# EtherCAT_Sheet.net
KiCad netlist of a schematic drawn in Altium Designer
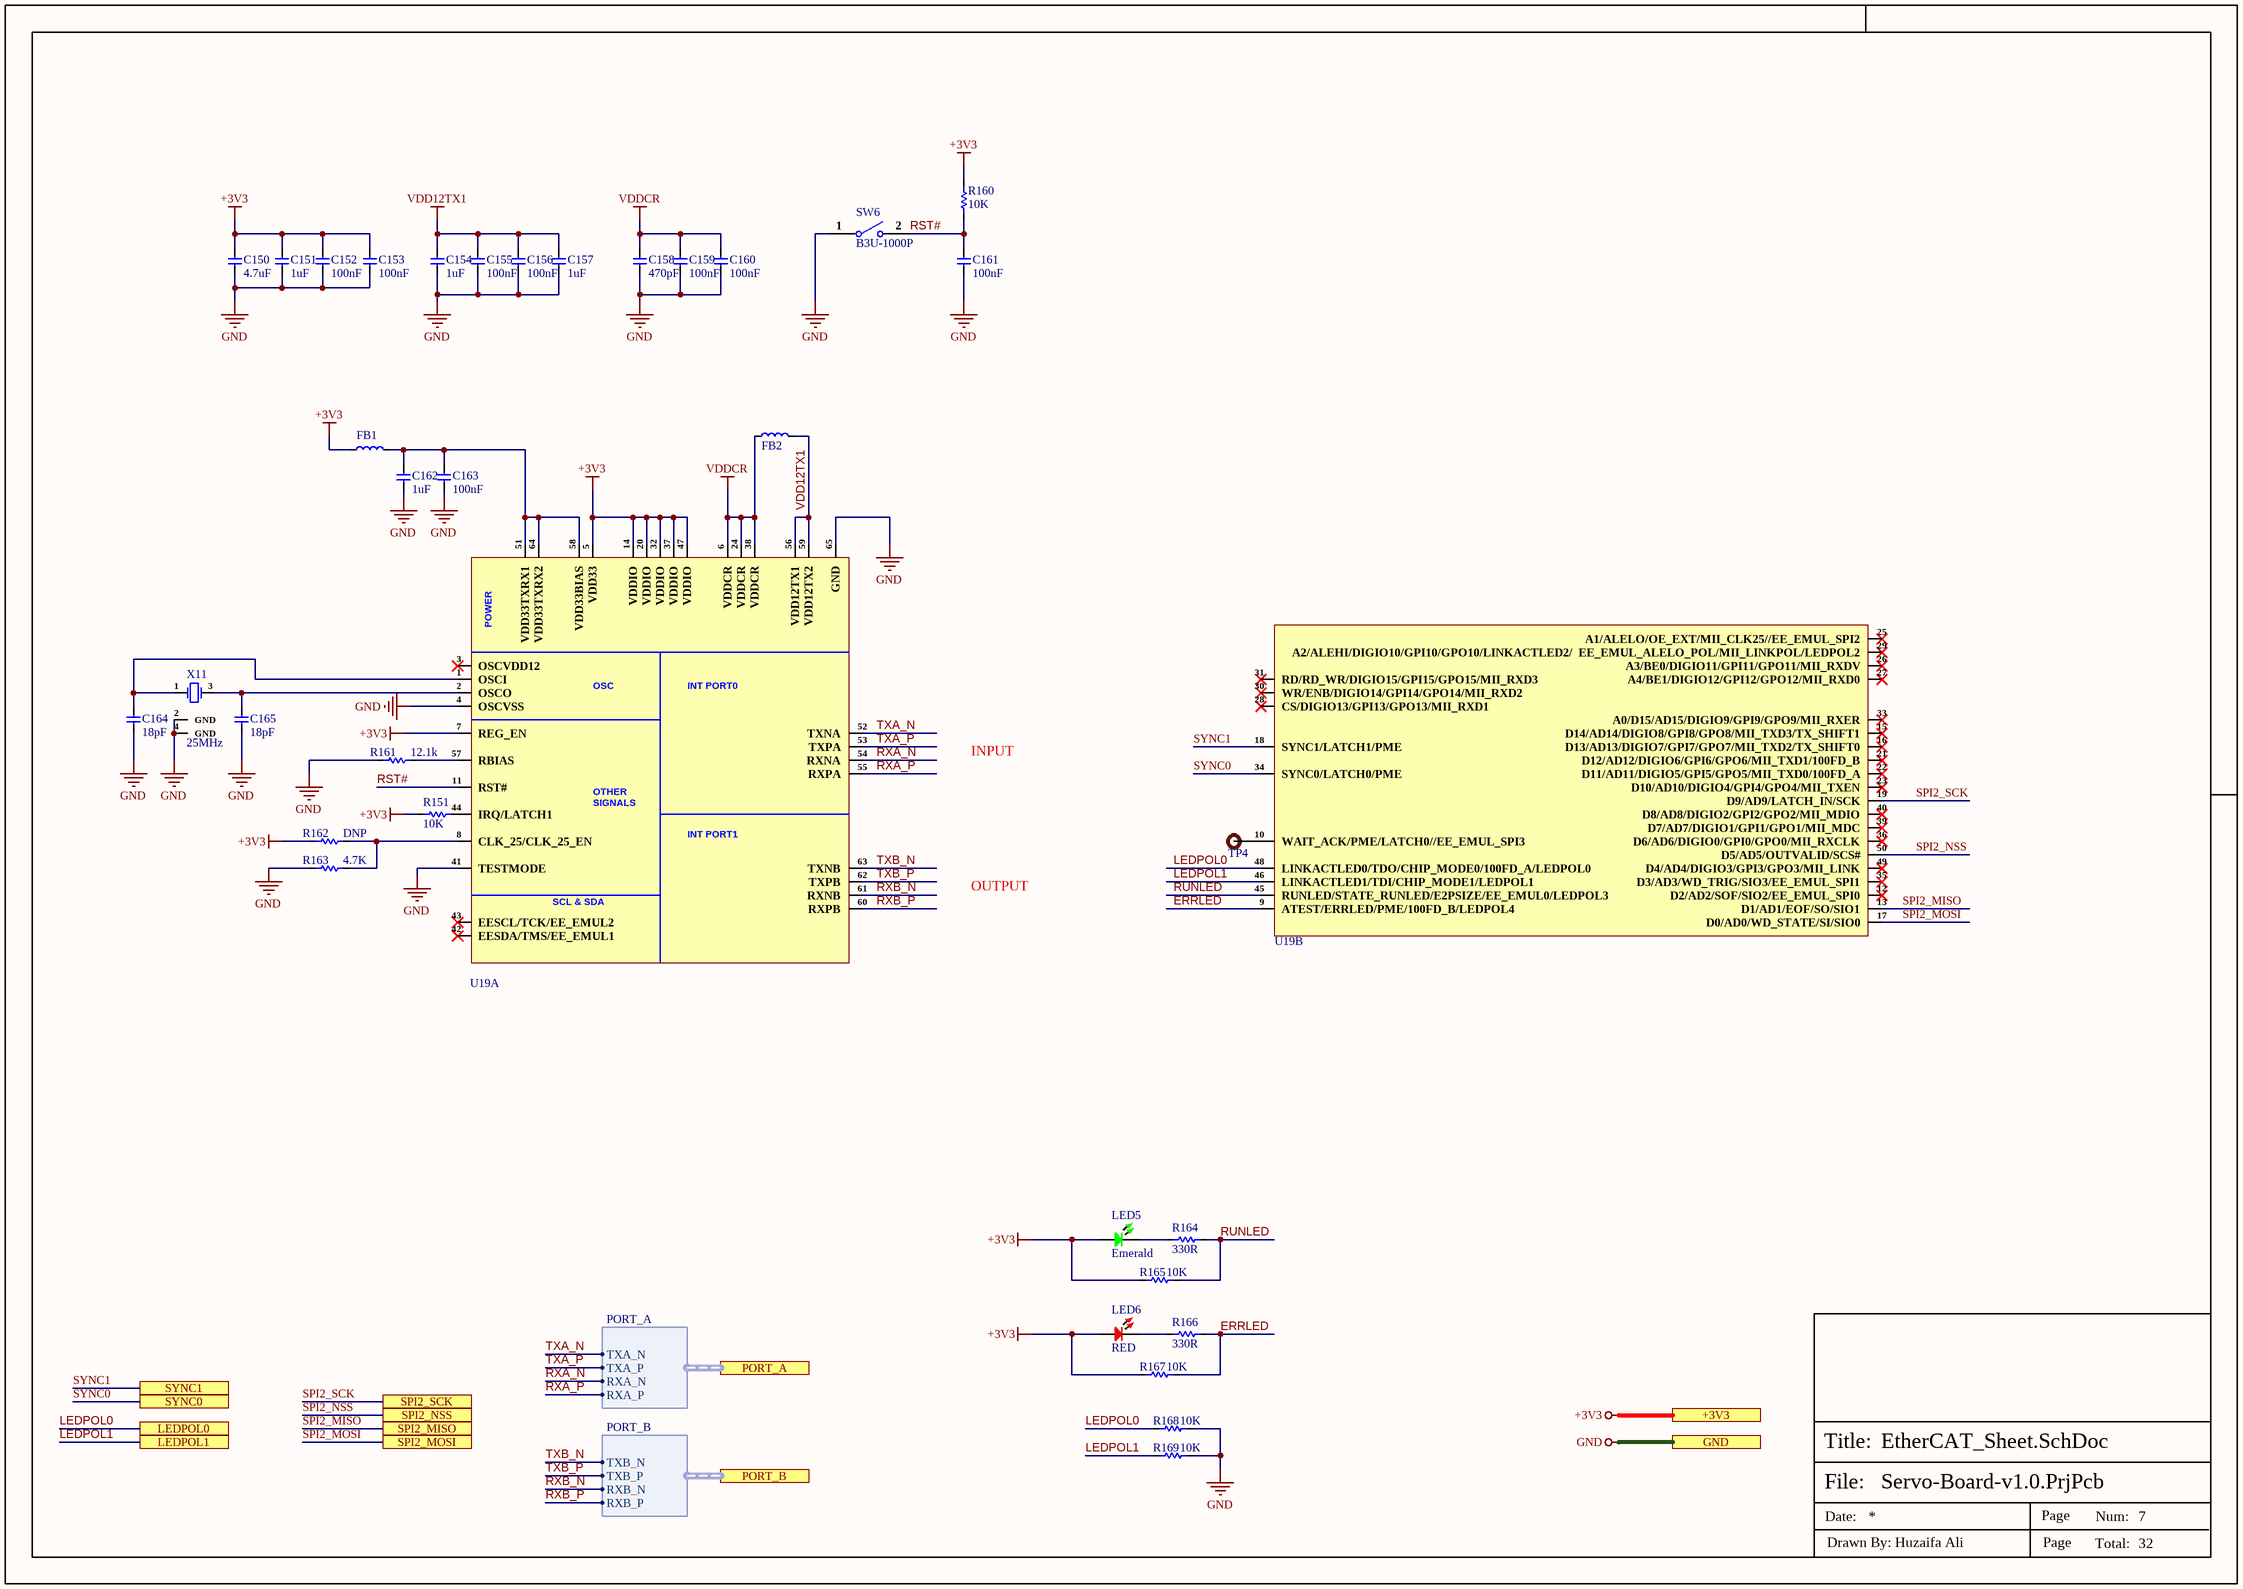
[diagram p0: EtherCAT_Sheet.SchDoc]

(export (version "E")
  (design (tool "Eeschema 10.0.6"))
  (components
    (comp (ref "C150")
      (value "4.7uF")
      (footprint "Cap-0402")
      (description "CAP CER 4.7UF 10V X5R 0402")
      (fields
        (field (name "MANUFACTURER") "Yageo")
        (field (name "MANUFACTURER PART NUMBER") "CC0402KRX5R6BB475")
      )
      (libsource (lib "eSpark Libraries") (part "CC0402KRX5R6BB475"))
    )
    (comp (ref "C151")
      (value "1uF")
      (footprint "Cap-0402")
      (description "CAP CER 1UF 10V X5R 0402")
      (fields
        (field (name "MANUFACTURER") "Yageo")
        (field (name "MANUFACTURER PART NUMBER") "CC0402KRX5R6BB105")
      )
      (libsource (lib "eSpark Libraries") (part "CC0402KRX5R6BB105"))
    )
    (comp (ref "C152")
      (value "100nF")
      (footprint "cap-0402")
      (description "CAP CER 0.1UF 50V X7R 0402")
      (fields
        (field (name "MANUFACTURER") "TDK")
        (field (name "MANUFACTURER PART NUMBER") "C1005X7R1H104KT000F")
      )
      (libsource (lib "eSpark Libraries") (part "C1005X7R1H104KT000F"))
    )
    (comp (ref "C153")
      (value "100nF")
      (footprint "cap-0402")
      (description "CAP CER 0.1UF 50V X7R 0402")
      (fields
        (field (name "MANUFACTURER") "TDK")
        (field (name "MANUFACTURER PART NUMBER") "C1005X7R1H104KT000F")
      )
      (libsource (lib "eSpark Libraries") (part "C1005X7R1H104KT000F"))
    )
    (comp (ref "C154")
      (value "1uF")
      (footprint "Cap-0402")
      (description "CAP CER 1UF 10V X5R 0402")
      (fields
        (field (name "MANUFACTURER") "Yageo")
        (field (name "MANUFACTURER PART NUMBER") "CC0402KRX5R6BB105")
      )
      (libsource (lib "eSpark Libraries") (part "CC0402KRX5R6BB105"))
    )
    (comp (ref "C155")
      (value "100nF")
      (footprint "cap-0402")
      (description "CAP CER 0.1UF 50V X7R 0402")
      (fields
        (field (name "MANUFACTURER") "TDK")
        (field (name "MANUFACTURER PART NUMBER") "C1005X7R1H104KT000F")
      )
      (libsource (lib "eSpark Libraries") (part "C1005X7R1H104KT000F"))
    )
    (comp (ref "C156")
      (value "100nF")
      (footprint "cap-0402")
      (description "CAP CER 0.1UF 50V X7R 0402")
      (fields
        (field (name "MANUFACTURER") "TDK")
        (field (name "MANUFACTURER PART NUMBER") "C1005X7R1H104KT000F")
      )
      (libsource (lib "eSpark Libraries") (part "C1005X7R1H104KT000F"))
    )
    (comp (ref "C157")
      (value "1uF")
      (footprint "Cap-0402")
      (description "CAP CER 1UF 10V X5R 0402")
      (fields
        (field (name "MANUFACTURER") "Yageo")
        (field (name "MANUFACTURER PART NUMBER") "CC0402KRX5R6BB105")
      )
      (libsource (lib "eSpark Libraries") (part "CC0402KRX5R6BB105"))
    )
    (comp (ref "C158")
      (value "470pF")
      (footprint "Cap-0603")
      (description "CAP CER 470PF 50V X7R 0603")
      (fields
        (field (name "MANUFACTURER") "Walsin Technologies")
        (field (name "MANUFACTURER PART NUMBER") "0603B471K500CT")
      )
      (libsource (lib "eSpark Libraries") (part "0603B471K500CT"))
    )
    (comp (ref "C159")
      (value "100nF")
      (footprint "cap-0402")
      (description "CAP CER 0.1UF 50V X7R 0402")
      (fields
        (field (name "MANUFACTURER") "TDK")
        (field (name "MANUFACTURER PART NUMBER") "C1005X7R1H104KT000F")
      )
      (libsource (lib "eSpark Libraries") (part "C1005X7R1H104KT000F"))
    )
    (comp (ref "C160")
      (value "100nF")
      (footprint "cap-0402")
      (description "CAP CER 0.1UF 50V X7R 0402")
      (fields
        (field (name "MANUFACTURER") "TDK")
        (field (name "MANUFACTURER PART NUMBER") "C1005X7R1H104KT000F")
      )
      (libsource (lib "eSpark Libraries") (part "C1005X7R1H104KT000F"))
    )
    (comp (ref "C161")
      (value "100nF")
      (footprint "cap-0402")
      (description "CAP CER 0.1UF 50V X7R 0402")
      (fields
        (field (name "MANUFACTURER") "TDK")
        (field (name "MANUFACTURER PART NUMBER") "C1005X7R1H104KT000F")
      )
      (libsource (lib "eSpark Libraries") (part "C1005X7R1H104KT000F"))
    )
    (comp (ref "C162")
      (value "1uF")
      (footprint "Cap-0402")
      (description "CAP CER 1UF 10V X5R 0402")
      (fields
        (field (name "MANUFACTURER") "Yageo")
        (field (name "MANUFACTURER PART NUMBER") "CC0402KRX5R6BB105")
      )
      (libsource (lib "eSpark Libraries") (part "CC0402KRX5R6BB105"))
    )
    (comp (ref "C163")
      (value "100nF")
      (footprint "cap-0402")
      (description "CAP CER 0.1UF 50V X7R 0402")
      (fields
        (field (name "MANUFACTURER") "TDK")
        (field (name "MANUFACTURER PART NUMBER") "C1005X7R1H104KT000F")
      )
      (libsource (lib "eSpark Libraries") (part "C1005X7R1H104KT000F"))
    )
    (comp (ref "C164")
      (value "18pF")
      (footprint "Cap-0402")
      (description "CAP CER 18PF 50V C0G/NP0 0402")
      (fields
        (field (name "MANUFACTURER") "Murata")
        (field (name "MANUFACTURER PART NUMBER") "GCM1555C1H180GA16D")
      )
      (libsource (lib "eSpark Libraries") (part "GCM1555C1H180GA16D"))
    )
    (comp (ref "C165")
      (value "18pF")
      (footprint "Cap-0402")
      (description "CAP CER 18PF 50V C0G/NP0 0402")
      (fields
        (field (name "MANUFACTURER") "Murata")
        (field (name "MANUFACTURER PART NUMBER") "GCM1555C1H180GA16D")
      )
      (libsource (lib "eSpark Libraries") (part "GCM1555C1H180GA16D"))
    )
    (comp (ref "FB1")
      (value "BLM15PG100SN1D")
      (footprint "IND-0402")
      (description "FERRITE BEAD 10 OHM 0402 1LN")
      (fields (field (name "MANUFACTURER") "Murata") (field (name "TOLERANCE") "25%"))
      (libsource (lib "eSpark Libraries") (part "BLM15PG100SN1D"))
    )
    (comp (ref "FB2")
      (value "BLM15PG100SN1D")
      (footprint "IND-0402")
      (description "FERRITE BEAD 10 OHM 0402 1LN")
      (fields (field (name "MANUFACTURER") "Murata") (field (name "TOLERANCE") "25%"))
      (libsource (lib "eSpark Libraries") (part "BLM15PG100SN1D"))
    )
    (comp (ref "LED5")
      (value "Emerald")
      (footprint "LED-0603")
      (description "Emerald 0603 Light Emitting Diodes (LED) ROHS")
      (fields
        (field (name "MANUFACTURER") "Foshan NationStar Optoelectronics")
        (field (name "MANUFACTURER PART NUMBER") "NCD0603G2")
      )
      (libsource (lib "eSpark Libraries") (part "NCD0603G2"))
    )
    (comp (ref "LED6")
      (value "RED")
      (footprint "LED-0603")
      (description "RED LED 0603 Light Emitting Diodes")
      (fields
        (field (name "MANUFACTURER") "Foshan NationStar Optoelectronics")
        (field (name "MANUFACTURER PART NUMBER") "NCD0603R3")
      )
      (libsource (lib "eSpark Libraries") (part "NCD0603R3"))
    )
    (comp (ref "R151")
      (value "10K")
      (footprint "Res-0402")
      (description "RES 10K OHM 1% 1/16W 0402")
      (fields
        (field (name "MANUFACTURER") "Yageo")
        (field (name "MANUFACTURER PART NUMBER") "RC0402FR-0710KL")
      )
      (libsource (lib "eSpark Libraries") (part "RC0402FR-0710KL"))
    )
    (comp (ref "R160")
      (value "10K")
      (footprint "Res-0402")
      (description "RES 10K OHM 1% 1/16W 0402")
      (fields
        (field (name "MANUFACTURER") "Yageo")
        (field (name "MANUFACTURER PART NUMBER") "RC0402FR-0710KL")
      )
      (libsource (lib "eSpark Libraries") (part "RC0402FR-0710KL"))
    )
    (comp (ref "R161")
      (value "12.1k")
      (footprint "Res-0402")
      (description "RES SMD 12.1KOHM 0.1% 1/16W 0402")
      (fields
        (field (name "MANUFACTURER") "Yageo")
        (field (name "MANUFACTURER PART NUMBER") "RT0402BRD0712K1L")
      )
      (libsource (lib "eSpark Libraries") (part "RT0402BRD0712K1L"))
    )
    (comp (ref "R162")
      (value "DNP")
      (footprint "Res-0402")
      (description "RES 4.7K OHM 1% 1/16W 0402")
      (fields
        (field (name "MANUFACTURER") "Yageo")
        (field (name "MANUFACTURER PART NUMBER") "RC0402FR-074K7L")
      )
      (libsource (lib "eSpark Libraries") (part "RC0402FR-074K7L"))
    )
    (comp (ref "R163")
      (value "4.7K")
      (footprint "Res-0402")
      (description "RES 4.7K OHM 1% 1/16W 0402")
      (fields
        (field (name "MANUFACTURER") "Yageo")
        (field (name "MANUFACTURER PART NUMBER") "RC0402FR-074K7L")
      )
      (libsource (lib "eSpark Libraries") (part "RC0402FR-074K7L"))
    )
    (comp (ref "R164")
      (value "330R")
      (footprint "Res-0603")
      (description "RES  SMD 330R 100 mW 0603")
      (fields
        (field (name "MANUFACTURER") "Yageo")
        (field (name "MANUFACTURER PART NUMBER") "RC0603JR-07330RL")
      )
      (libsource (lib "eSpark Libraries") (part "RC0603JR-07330RL"))
    )
    (comp (ref "R165")
      (value "10K")
      (footprint "Res-0402")
      (description "RES 10K OHM 1% 1/16W 0402")
      (fields
        (field (name "MANUFACTURER") "Yageo")
        (field (name "MANUFACTURER PART NUMBER") "RC0402FR-0710KL")
      )
      (libsource (lib "eSpark Libraries") (part "RC0402FR-0710KL"))
    )
    (comp (ref "R166")
      (value "330R")
      (footprint "Res-0603")
      (description "RES  SMD 330R 100 mW 0603")
      (fields
        (field (name "MANUFACTURER") "Yageo")
        (field (name "MANUFACTURER PART NUMBER") "RC0603JR-07330RL")
      )
      (libsource (lib "eSpark Libraries") (part "RC0603JR-07330RL"))
    )
    (comp (ref "R167")
      (value "10K")
      (footprint "Res-0402")
      (description "RES 10K OHM 1% 1/16W 0402")
      (fields
        (field (name "MANUFACTURER") "Yageo")
        (field (name "MANUFACTURER PART NUMBER") "RC0402FR-0710KL")
      )
      (libsource (lib "eSpark Libraries") (part "RC0402FR-0710KL"))
    )
    (comp (ref "R168")
      (value "10K")
      (footprint "Res-0402")
      (description "RES 10K OHM 1% 1/16W 0402")
      (fields
        (field (name "MANUFACTURER") "Yageo")
        (field (name "MANUFACTURER PART NUMBER") "RC0402FR-0710KL")
      )
      (libsource (lib "eSpark Libraries") (part "RC0402FR-0710KL"))
    )
    (comp (ref "R169")
      (value "10K")
      (footprint "Res-0402")
      (description "RES 10K OHM 1% 1/16W 0402")
      (fields
        (field (name "MANUFACTURER") "Yageo")
        (field (name "MANUFACTURER PART NUMBER") "RC0402FR-0710KL")
      )
      (libsource (lib "eSpark Libraries") (part "RC0402FR-0710KL"))
    )
    (comp (ref "SW6")
      (value "B3U-1000P")
      (footprint "B3U-1000P")
      (description "SWITCH TACTILE SPST-NO 0.05A 12V")
      (fields (field (name "MANUFACTURER") "Omron") (field (name "LCSC PART NUMBER") "C231329"))
      (libsource (lib "eSpark Libraries") (part "B3U-1000P"))
    )
    (comp (ref "TP4")
      (value "TEST POINT")
      (footprint "Test-point")
      (description "Test Point ON")
      (libsource (lib "eSpark Libraries") (part "TEST POINT"))
    )
    (comp (ref "U19")
      (value "LAN9253-SVB QFN64")
      (footprint "QFN-64-EP(9x9)")
      (description "2/3-PORT ETHERCAT SLAVE CTLR")
      (fields
        (field (name "MANUFACTURER") "Microchip")
        (field (name "MANUFACTURER PART NUMBER") "LAN9253-I/R4X")
      )
      (libsource (lib "eSpark Libraries") (part "LAN9253-SVB QFN64"))
    )
    (comp (ref "X11")
      (value "25MHz")
      (footprint "SMD3225-4P")
      (description "25MHz 贴片晶振 18pF ±10ppm ±20ppm SMD3225-4P Crystals ROHS")
      (fields (field (name "LCSC PART NUMBER") "C70593") (field (name "MANUFACTURER") "YXC"))
      (libsource (lib "eSpark Libraries") (part "X322525MRB4SI"))
    )
  )
  (nets
    (net (code "3") (name "+3V3") (class "Default")
      (node (ref "C150") (pin "2") (pinfunction "2_2") (pintype "passive"))
      (node (ref "C151") (pin "2") (pinfunction "2_2") (pintype "passive"))
      (node (ref "C152") (pin "2") (pinfunction "2_2") (pintype "passive"))
      (node (ref "C153") (pin "2") (pinfunction "2_2") (pintype "passive"))
      (node (ref "FB1") (pin "1") (pinfunction "1_1") (pintype "passive"))
      (node (ref "LED5") (pin "1") (pinfunction "1_1") (pintype "passive"))
      (node (ref "LED6") (pin "1") (pinfunction "1_1") (pintype "passive"))
      (node (ref "R151") (pin "1") (pinfunction "1_1") (pintype "passive"))
      (node (ref "R160") (pin "1") (pinfunction "1_1") (pintype "passive"))
      (node (ref "R162") (pin "1") (pinfunction "1_1") (pintype "passive"))
      (node (ref "R165") (pin "2") (pinfunction "2_2") (pintype "passive"))
      (node (ref "R167") (pin "2") (pinfunction "2_2") (pintype "passive"))
      (node (ref "U19") (pin "14") (pinfunction "VDDIO_14") (pintype "passive"))
      (node (ref "U19") (pin "20") (pinfunction "VDDIO_20") (pintype "passive"))
      (node (ref "U19") (pin "32") (pinfunction "VDDIO_32") (pintype "passive"))
      (node (ref "U19") (pin "37") (pinfunction "VDDIO_37") (pintype "passive"))
      (node (ref "U19") (pin "47") (pinfunction "VDDIO_47") (pintype "passive"))
      (node (ref "U19") (pin "5") (pinfunction "VDD33_5") (pintype "passive"))
      (node (ref "U19") (pin "7") (pinfunction "REG_EN_7") (pintype "passive"))
    )
    (net (code "4") (name "/ERRLED") (class "Default")
      (node (ref "R166") (pin "2") (pinfunction "2_2") (pintype "passive"))
      (node (ref "R167") (pin "1") (pinfunction "1_1") (pintype "passive"))
      (node (ref "U19") (pin "9") (pinfunction "ATEST/ERRLED/PME/100FD_B/LEDPOL4_9") (pintype "passive"))
    )
    (net (code "5") (name "/LEDPOL0") (class "Default")
      (node (ref "R168") (pin "2") (pinfunction "2_2") (pintype "passive"))
      (node (ref "U19") (pin "48") (pinfunction "LINKACTLED0/TDO/CHIP_MODE0/100FD_A/LEDPOL0_48") (pintype "passive"))
    )
    (net (code "6") (name "/LEDPOL1") (class "Default")
      (node (ref "R169") (pin "2") (pinfunction "2_2") (pintype "passive"))
      (node (ref "U19") (pin "46") (pinfunction "LINKACTLED1/TDI/CHIP_MODE1/LEDPOL1_46") (pintype "passive"))
    )
    (net (code "7") (name "/RST#") (class "Default")
      (node (ref "C161") (pin "2") (pinfunction "2_2") (pintype "passive"))
      (node (ref "R160") (pin "2") (pinfunction "2_2") (pintype "passive"))
      (node (ref "SW6") (pin "2") (pinfunction "2_2") (pintype "passive"))
      (node (ref "U19") (pin "11") (pinfunction "RST#_11") (pintype "passive"))
    )
    (net (code "8") (name "/RUNLED") (class "Default")
      (node (ref "R164") (pin "2") (pinfunction "2_2") (pintype "passive"))
      (node (ref "R165") (pin "1") (pinfunction "1_1") (pintype "passive"))
      (node (ref "U19") (pin "45") (pinfunction "RUNLED/STATE_RUNLED/E2PSIZE/EE_EMUL0/LEDPOL3_45") (pintype "passive"))
    )
    (net (code "9") (name "/RXA_N") (class "Default")
      (node (ref "U19") (pin "54") (pinfunction "RXNA_54") (pintype "passive"))
    )
    (net (code "10") (name "/RXA_P") (class "Default")
      (node (ref "U19") (pin "55") (pinfunction "RXPA_55") (pintype "passive"))
    )
    (net (code "11") (name "/RXB_N") (class "Default")
      (node (ref "U19") (pin "61") (pinfunction "RXNB_61") (pintype "passive"))
    )
    (net (code "12") (name "/RXB_P") (class "Default")
      (node (ref "U19") (pin "60") (pinfunction "RXPB_60") (pintype "passive"))
    )
    (net (code "13") (name "/SPI2_MISO") (class "Default")
      (node (ref "U19") (pin "13") (pinfunction "D1/AD1/EOF/SO/SIO1_13") (pintype "passive"))
    )
    (net (code "14") (name "/SPI2_MOSI") (class "Default")
      (node (ref "U19") (pin "17") (pinfunction "D0/AD0/WD_STATE/SI/SIO0_17") (pintype "passive"))
    )
    (net (code "15") (name "/SPI2_NSS") (class "Default")
      (node (ref "U19") (pin "50") (pinfunction "D5/AD5/OUTVALID/SCS#_50") (pintype "passive"))
    )
    (net (code "16") (name "/SPI2_SCK") (class "Default")
      (node (ref "U19") (pin "19") (pinfunction "D9/AD9/LATCH_IN/SCK_19") (pintype "passive"))
    )
    (net (code "17") (name "/SYNC0") (class "Default")
      (node (ref "U19") (pin "34") (pinfunction "SYNC0/LATCH0/PME_34") (pintype "passive"))
    )
    (net (code "18") (name "/SYNC1") (class "Default")
      (node (ref "U19") (pin "18") (pinfunction "SYNC1/LATCH1/PME_18") (pintype "passive"))
    )
    (net (code "19") (name "/TXA_N") (class "Default")
      (node (ref "U19") (pin "52") (pinfunction "TXNA_52") (pintype "passive"))
    )
    (net (code "20") (name "/TXA_P") (class "Default")
      (node (ref "U19") (pin "53") (pinfunction "TXPA_53") (pintype "passive"))
    )
    (net (code "21") (name "/TXB_N") (class "Default")
      (node (ref "U19") (pin "63") (pinfunction "TXNB_63") (pintype "passive"))
    )
    (net (code "22") (name "/TXB_P") (class "Default")
      (node (ref "U19") (pin "62") (pinfunction "TXPB_62") (pintype "passive"))
    )
    (net (code "25") (name "GND") (class "Default")
      (node (ref "C150") (pin "1") (pinfunction "1_1") (pintype "passive"))
      (node (ref "C151") (pin "1") (pinfunction "1_1") (pintype "passive"))
      (node (ref "C152") (pin "1") (pinfunction "1_1") (pintype "passive"))
      (node (ref "C153") (pin "1") (pinfunction "1_1") (pintype "passive"))
      (node (ref "C154") (pin "1") (pinfunction "1_1") (pintype "passive"))
      (node (ref "C155") (pin "1") (pinfunction "1_1") (pintype "passive"))
      (node (ref "C156") (pin "1") (pinfunction "1_1") (pintype "passive"))
      (node (ref "C157") (pin "1") (pinfunction "1_1") (pintype "passive"))
      (node (ref "C158") (pin "1") (pinfunction "1_1") (pintype "passive"))
      (node (ref "C159") (pin "1") (pinfunction "1_1") (pintype "passive"))
      (node (ref "C160") (pin "1") (pinfunction "1_1") (pintype "passive"))
      (node (ref "C161") (pin "1") (pinfunction "1_1") (pintype "passive"))
      (node (ref "C162") (pin "1") (pinfunction "1_1") (pintype "passive"))
      (node (ref "C163") (pin "1") (pinfunction "1_1") (pintype "passive"))
      (node (ref "C164") (pin "2") (pinfunction "2_2") (pintype "passive"))
      (node (ref "C165") (pin "2") (pinfunction "2_2") (pintype "passive"))
      (node (ref "R161") (pin "1") (pinfunction "1_1") (pintype "passive"))
      (node (ref "R163") (pin "1") (pinfunction "1_1") (pintype "passive"))
      (node (ref "R168") (pin "1") (pinfunction "1_1") (pintype "passive"))
      (node (ref "R169") (pin "1") (pinfunction "1_1") (pintype "passive"))
      (node (ref "SW6") (pin "1") (pinfunction "1_1") (pintype "passive"))
      (node (ref "U19") (pin "4") (pinfunction "OSCVSS_4") (pintype "passive"))
      (node (ref "U19") (pin "41") (pinfunction "TESTMODE_41") (pintype "passive"))
      (node (ref "U19") (pin "65") (pinfunction "GND_65") (pintype "passive"))
      (node (ref "X11") (pin "2") (pinfunction "GND_2") (pintype "passive"))
      (node (ref "X11") (pin "4") (pinfunction "GND_4") (pintype "passive"))
    )
    (net (code "26") (name "Net-(LED5-Pad2)") (class "Default")
      (node (ref "LED5") (pin "2") (pinfunction "2_2") (pintype "passive"))
      (node (ref "R164") (pin "1") (pinfunction "1_1") (pintype "passive"))
    )
    (net (code "27") (name "Net-(LED6-Pad2)") (class "Default")
      (node (ref "LED6") (pin "2") (pinfunction "2_2") (pintype "passive"))
      (node (ref "R166") (pin "1") (pinfunction "1_1") (pintype "passive"))
    )
    (net (code "28") (name "Net-(U19A-CLK_25{slash}CLK_25_EN)") (class "Default")
      (node (ref "R162") (pin "2") (pinfunction "2_2") (pintype "passive"))
      (node (ref "R163") (pin "2") (pinfunction "2_2") (pintype "passive"))
      (node (ref "U19") (pin "8") (pinfunction "CLK_25/CLK_25_EN_8") (pintype "passive"))
    )
    (net (code "29") (name "Net-(U19A-IRQ{slash}LATCH1)") (class "Default")
      (node (ref "R151") (pin "2") (pinfunction "2_2") (pintype "passive"))
      (node (ref "U19") (pin "44") (pinfunction "IRQ/LATCH1_44") (pintype "passive"))
    )
    (net (code "30") (name "Net-(U19A-OSCI)") (class "Default")
      (node (ref "C164") (pin "1") (pinfunction "1_1") (pintype "passive"))
      (node (ref "U19") (pin "1") (pinfunction "OSCI_1") (pintype "passive"))
      (node (ref "X11") (pin "1") (pinfunction "CRYSTAL_1") (pintype "passive"))
    )
    (net (code "31") (name "Net-(U19A-OSCO)") (class "Default")
      (node (ref "C165") (pin "1") (pinfunction "1_1") (pintype "passive"))
      (node (ref "U19") (pin "2") (pinfunction "OSCO_2") (pintype "passive"))
      (node (ref "X11") (pin "3") (pinfunction "CRYSTAL_3") (pintype "passive"))
    )
    (net (code "32") (name "Net-(U19A-RBIAS)") (class "Default")
      (node (ref "R161") (pin "2") (pinfunction "2_2") (pintype "passive"))
      (node (ref "U19") (pin "57") (pinfunction "RBIAS_57") (pintype "passive"))
    )
    (net (code "33") (name "Net-(U19A-VDD33BIAS)") (class "Default")
      (node (ref "C162") (pin "2") (pinfunction "2_2") (pintype "passive"))
      (node (ref "C163") (pin "2") (pinfunction "2_2") (pintype "passive"))
      (node (ref "FB1") (pin "2") (pinfunction "2_2") (pintype "passive"))
      (node (ref "U19") (pin "51") (pinfunction "VDD33TXRX1_51") (pintype "passive"))
      (node (ref "U19") (pin "58") (pinfunction "VDD33BIAS_58") (pintype "passive"))
      (node (ref "U19") (pin "64") (pinfunction "VDD33TXRX2_64") (pintype "passive"))
    )
    (net (code "34") (name "Net-(U19B-WAIT_ACK{slash}PME{slash}LATCH0{slash}{slash}EE_EMUL_SPI3)") (class "Default")
      (node (ref "TP4") (pin "1") (pinfunction "1_1") (pintype "passive"))
      (node (ref "U19") (pin "10") (pinfunction "WAIT_ACK/PME/LATCH0//EE_EMUL_SPI3_10") (pintype "passive"))
    )
    (net (code "35") (name "VDD12TX1") (class "Default")
      (node (ref "C154") (pin "2") (pinfunction "2_2") (pintype "passive"))
      (node (ref "C155") (pin "2") (pinfunction "2_2") (pintype "passive"))
      (node (ref "C156") (pin "2") (pinfunction "2_2") (pintype "passive"))
      (node (ref "C157") (pin "2") (pinfunction "2_2") (pintype "passive"))
      (node (ref "FB2") (pin "2") (pinfunction "2_2") (pintype "passive"))
      (node (ref "U19") (pin "56") (pinfunction "VDD12TX1_56") (pintype "passive"))
      (node (ref "U19") (pin "59") (pinfunction "VDD12TX2_59") (pintype "passive"))
    )
    (net (code "36") (name "VDDCR") (class "Default")
      (node (ref "C158") (pin "2") (pinfunction "2_2") (pintype "passive"))
      (node (ref "C159") (pin "2") (pinfunction "2_2") (pintype "passive"))
      (node (ref "C160") (pin "2") (pinfunction "2_2") (pintype "passive"))
      (node (ref "FB2") (pin "1") (pinfunction "1_1") (pintype "passive"))
      (node (ref "U19") (pin "24") (pinfunction "VDDCR_24") (pintype "passive"))
      (node (ref "U19") (pin "38") (pinfunction "VDDCR_38") (pintype "passive"))
      (node (ref "U19") (pin "6") (pinfunction "VDDCR_6") (pintype "passive"))
    )
    (net (code "37") (name "unconnected-(U19A-EESCL{slash}TCK{slash}EE_EMUL2-Pad43)") (class "Default")
      (node (ref "U19") (pin "43") (pinfunction "EESCL/TCK/EE_EMUL2_43") (pintype "passive+no_connect"))
    )
    (net (code "38") (name "unconnected-(U19A-EESDA{slash}TMS{slash}EE_EMUL1-Pad42)") (class "Default")
      (node (ref "U19") (pin "42") (pinfunction "EESDA/TMS/EE_EMUL1_42") (pintype "passive+no_connect"))
    )
    (net (code "39") (name "unconnected-(U19A-OSCVDD12-Pad3)") (class "Default")
      (node (ref "U19") (pin "3") (pinfunction "OSCVDD12_3") (pintype "passive+no_connect"))
    )
    (net (code "40") (name "unconnected-(U19B-A0{slash}D15{slash}AD15{slash}DIGIO9{slash}GPI9{slash}GPO9{slash}MII_RXER-Pad33)") (class "Default")
      (node (ref "U19") (pin "33") (pinfunction "A0/D15/AD15/DIGIO9/GPI9/GPO9/MII_RXER_33") (pintype "passive+no_connect"))
    )
    (net (code "41") (name "unconnected-(U19B-A1{slash}ALELO{slash}OE_EXT{slash}MII_CLK25{slash}{slash}EE_EMUL_SPI2-Pad25)") (class "Default")
      (node (ref "U19") (pin "25") (pinfunction "A1/ALELO/OE_EXT/MII_CLK25//EE_EMUL_SPI2_25") (pintype "passive+no_connect"))
    )
    (net (code "42") (name "unconnected-(U19B-A2{slash}ALEHI{slash}DIGIO10{slash}GPI10{slash}GPO10{slash}LINKACTLED2{slash}__EE_EMUL_ALELO_POL{slash}MII_LINKPOL{slash}LEDPOL2-Pad29)") (class "Default")
      (node (ref "U19") (pin "29") (pinfunction "A2/ALEHI/DIGIO10/GPI10/GPO10/LINKACTLED2/__EE_EMUL_ALELO_POL/MII_LINKPOL/LEDPOL2_29") (pintype "passive+no_connect"))
    )
    (net (code "43") (name "unconnected-(U19B-A3{slash}BE0{slash}DIGIO11{slash}GPI11{slash}GPO11{slash}MII_RXDV-Pad26)") (class "Default")
      (node (ref "U19") (pin "26") (pinfunction "A3/BE0/DIGIO11/GPI11/GPO11/MII_RXDV_26") (pintype "passive+no_connect"))
    )
    (net (code "44") (name "unconnected-(U19B-A4{slash}BE1{slash}DIGIO12{slash}GPI12{slash}GPO12{slash}MII_RXD0-Pad27)") (class "Default")
      (node (ref "U19") (pin "27") (pinfunction "A4/BE1/DIGIO12/GPI12/GPO12/MII_RXD0_27") (pintype "passive+no_connect"))
    )
    (net (code "45") (name "unconnected-(U19B-CS{slash}DIGIO13{slash}GPI13{slash}GPO13{slash}MII_RXD1-Pad28)") (class "Default")
      (node (ref "U19") (pin "28") (pinfunction "CS/DIGIO13/GPI13/GPO13/MII_RXD1_28") (pintype "passive+no_connect"))
    )
    (net (code "46") (name "unconnected-(U19B-D2{slash}AD2{slash}SOF{slash}SIO2{slash}EE_EMUL_SPI0-Pad12)") (class "Default")
      (node (ref "U19") (pin "12") (pinfunction "D2/AD2/SOF/SIO2/EE_EMUL_SPI0_12") (pintype "passive+no_connect"))
    )
    (net (code "47") (name "unconnected-(U19B-D3{slash}AD3{slash}WD_TRIG{slash}SIO3{slash}EE_EMUL_SPI1-Pad35)") (class "Default")
      (node (ref "U19") (pin "35") (pinfunction "D3/AD3/WD_TRIG/SIO3/EE_EMUL_SPI1_35") (pintype "passive+no_connect"))
    )
    (net (code "48") (name "unconnected-(U19B-D4{slash}AD4{slash}DIGIO3{slash}GPI3{slash}GPO3{slash}MII_LINK-Pad49)") (class "Default")
      (node (ref "U19") (pin "49") (pinfunction "D4/AD4/DIGIO3/GPI3/GPO3/MII_LINK_49") (pintype "passive+no_connect"))
    )
    (net (code "49") (name "unconnected-(U19B-D6{slash}AD6{slash}DIGIO0{slash}GPI0{slash}GPO0{slash}MII_RXCLK-Pad36)") (class "Default")
      (node (ref "U19") (pin "36") (pinfunction "D6/AD6/DIGIO0/GPI0/GPO0/MII_RXCLK_36") (pintype "passive+no_connect"))
    )
    (net (code "50") (name "unconnected-(U19B-D7{slash}AD7{slash}DIGIO1{slash}GPI1{slash}GPO1{slash}MII_MDC-Pad39)") (class "Default")
      (node (ref "U19") (pin "39") (pinfunction "D7/AD7/DIGIO1/GPI1/GPO1/MII_MDC_39") (pintype "passive+no_connect"))
    )
    (net (code "51") (name "unconnected-(U19B-D8{slash}AD8{slash}DIGIO2{slash}GPI2{slash}GPO2{slash}MII_MDIO-Pad40)") (class "Default")
      (node (ref "U19") (pin "40") (pinfunction "D8/AD8/DIGIO2/GPI2/GPO2/MII_MDIO_40") (pintype "passive+no_connect"))
    )
    (net (code "52") (name "unconnected-(U19B-D10{slash}AD10{slash}DIGIO4{slash}GPI4{slash}GPO4{slash}MII_TXEN-Pad23)") (class "Default")
      (node (ref "U19") (pin "23") (pinfunction "D10/AD10/DIGIO4/GPI4/GPO4/MII_TXEN_23") (pintype "passive+no_connect"))
    )
    (net (code "53") (name "unconnected-(U19B-D11{slash}AD11{slash}DIGIO5{slash}GPI5{slash}GPO5{slash}MII_TXD0{slash}100FD_A-Pad22)") (class "Default")
      (node (ref "U19") (pin "22") (pinfunction "D11/AD11/DIGIO5/GPI5/GPO5/MII_TXD0/100FD_A_22") (pintype "passive+no_connect"))
    )
    (net (code "54") (name "unconnected-(U19B-D12{slash}AD12{slash}DIGIO6{slash}GPI6{slash}GPO6{slash}MII_TXD1{slash}100FD_B-Pad21)") (class "Default")
      (node (ref "U19") (pin "21") (pinfunction "D12/AD12/DIGIO6/GPI6/GPO6/MII_TXD1/100FD_B_21") (pintype "passive+no_connect"))
    )
    (net (code "55") (name "unconnected-(U19B-D13{slash}AD13{slash}DIGIO7{slash}GPI7{slash}GPO7{slash}MII_TXD2{slash}TX_SHIFT0-Pad16)") (class "Default")
      (node (ref "U19") (pin "16") (pinfunction "D13/AD13/DIGIO7/GPI7/GPO7/MII_TXD2/TX_SHIFT0_16") (pintype "passive+no_connect"))
    )
    (net (code "56") (name "unconnected-(U19B-D14{slash}AD14{slash}DIGIO8{slash}GPI8{slash}GPO8{slash}MII_TXD3{slash}TX_SHIFT1-Pad15)") (class "Default")
      (node (ref "U19") (pin "15") (pinfunction "D14/AD14/DIGIO8/GPI8/GPO8/MII_TXD3/TX_SHIFT1_15") (pintype "passive+no_connect"))
    )
    (net (code "57") (name "unconnected-(U19B-RD{slash}RD_WR{slash}DIGIO15{slash}GPI15{slash}GPO15{slash}MII_RXD3-Pad31)") (class "Default")
      (node (ref "U19") (pin "31") (pinfunction "RD/RD_WR/DIGIO15/GPI15/GPO15/MII_RXD3_31") (pintype "passive+no_connect"))
    )
    (net (code "58") (name "unconnected-(U19B-WR{slash}ENB{slash}DIGIO14{slash}GPI14{slash}GPO14{slash}MII_RXD2-Pad30)") (class "Default")
      (node (ref "U19") (pin "30") (pinfunction "WR/ENB/DIGIO14/GPI14/GPO14/MII_RXD2_30") (pintype "passive+no_connect"))
    )
  )
)
